# MakeSpaceBadge-2.net
KiCad netlist of a schematic drawn in EAGLE
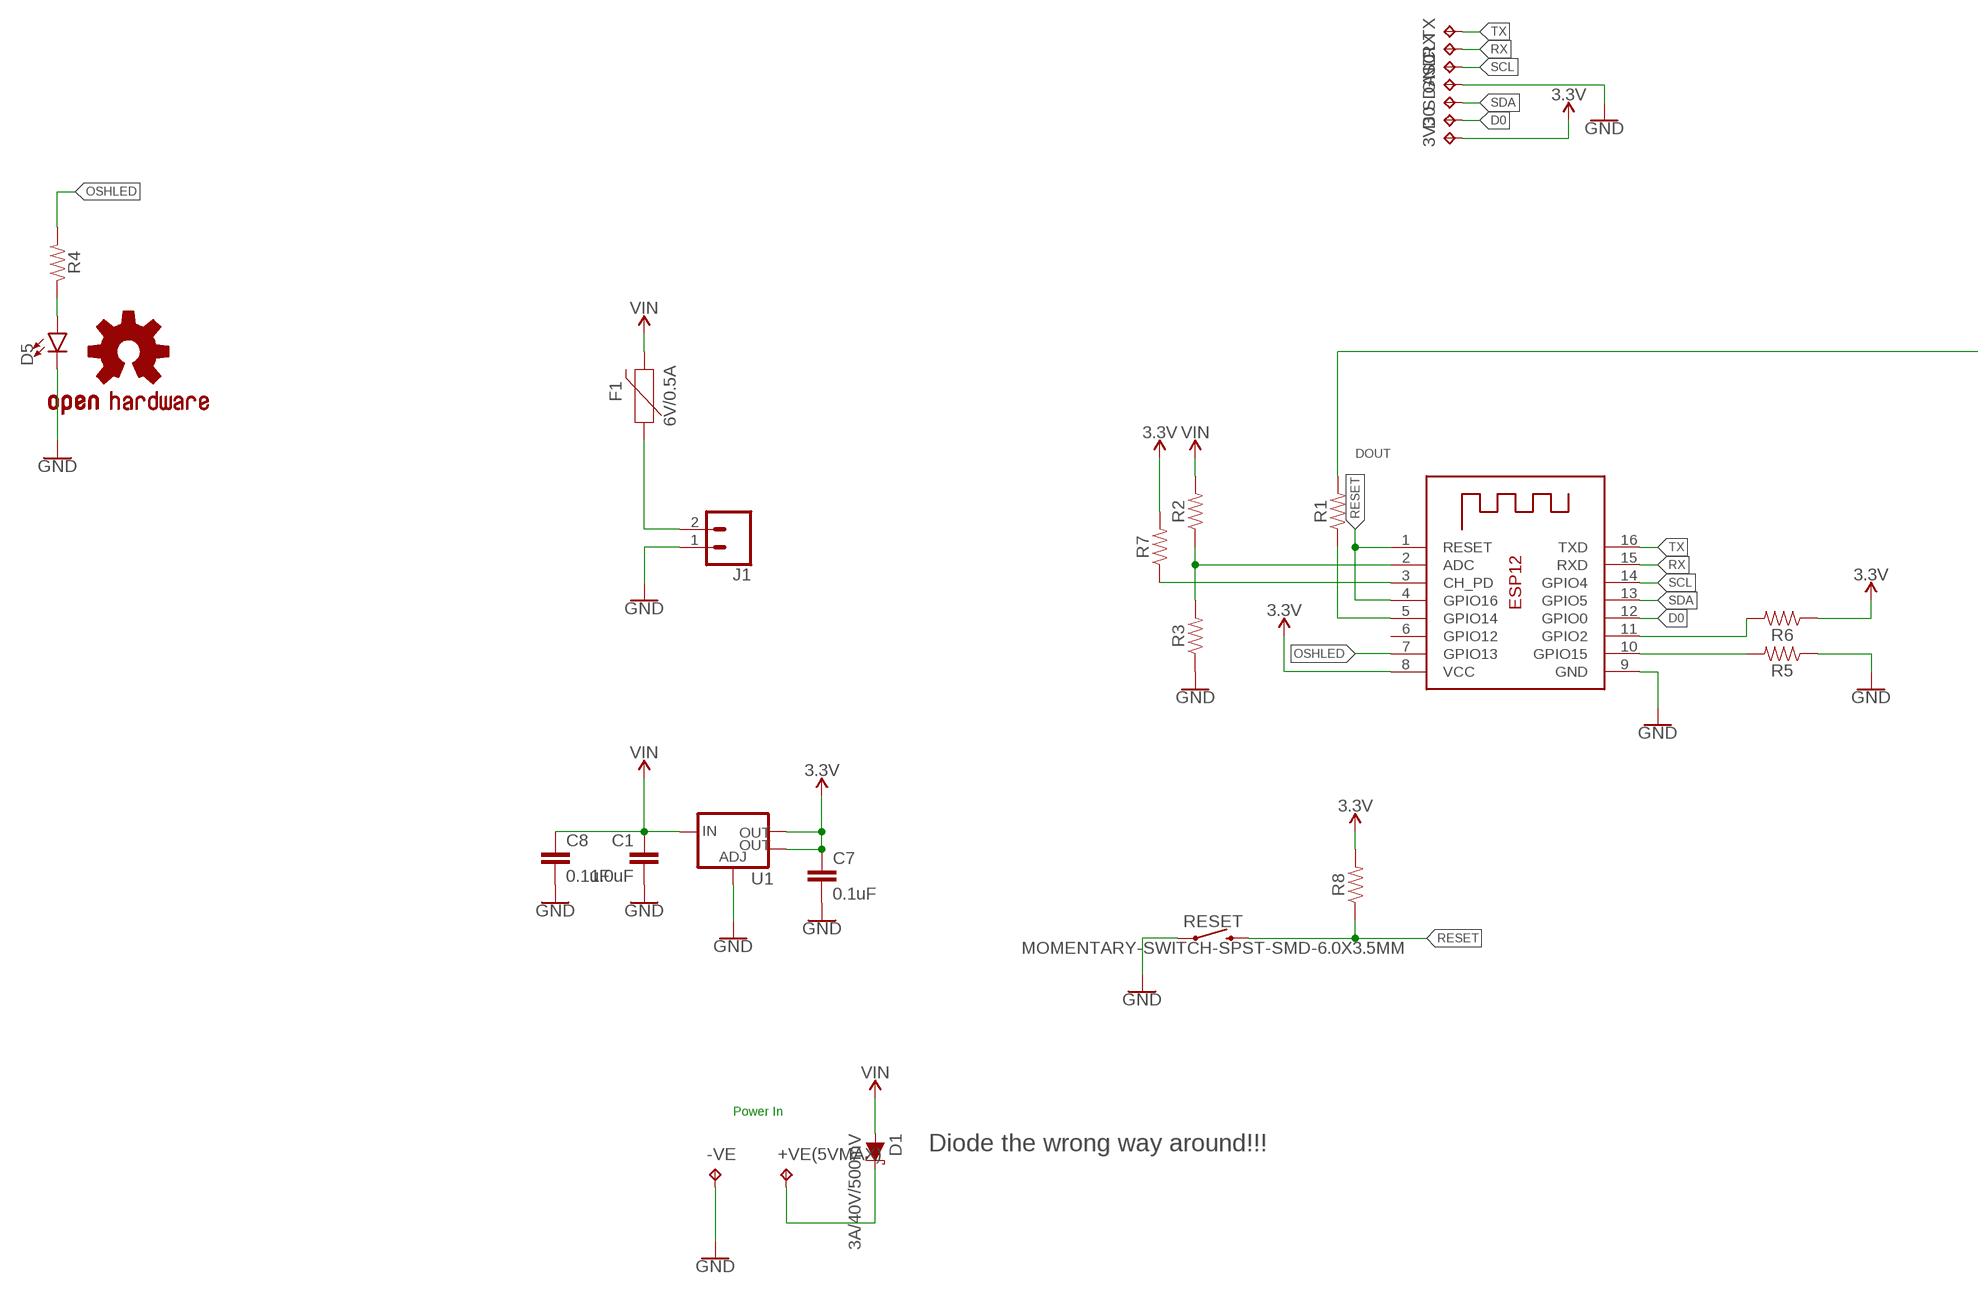
[diagram p0: schematic, sheet 1, part 1 of 2]
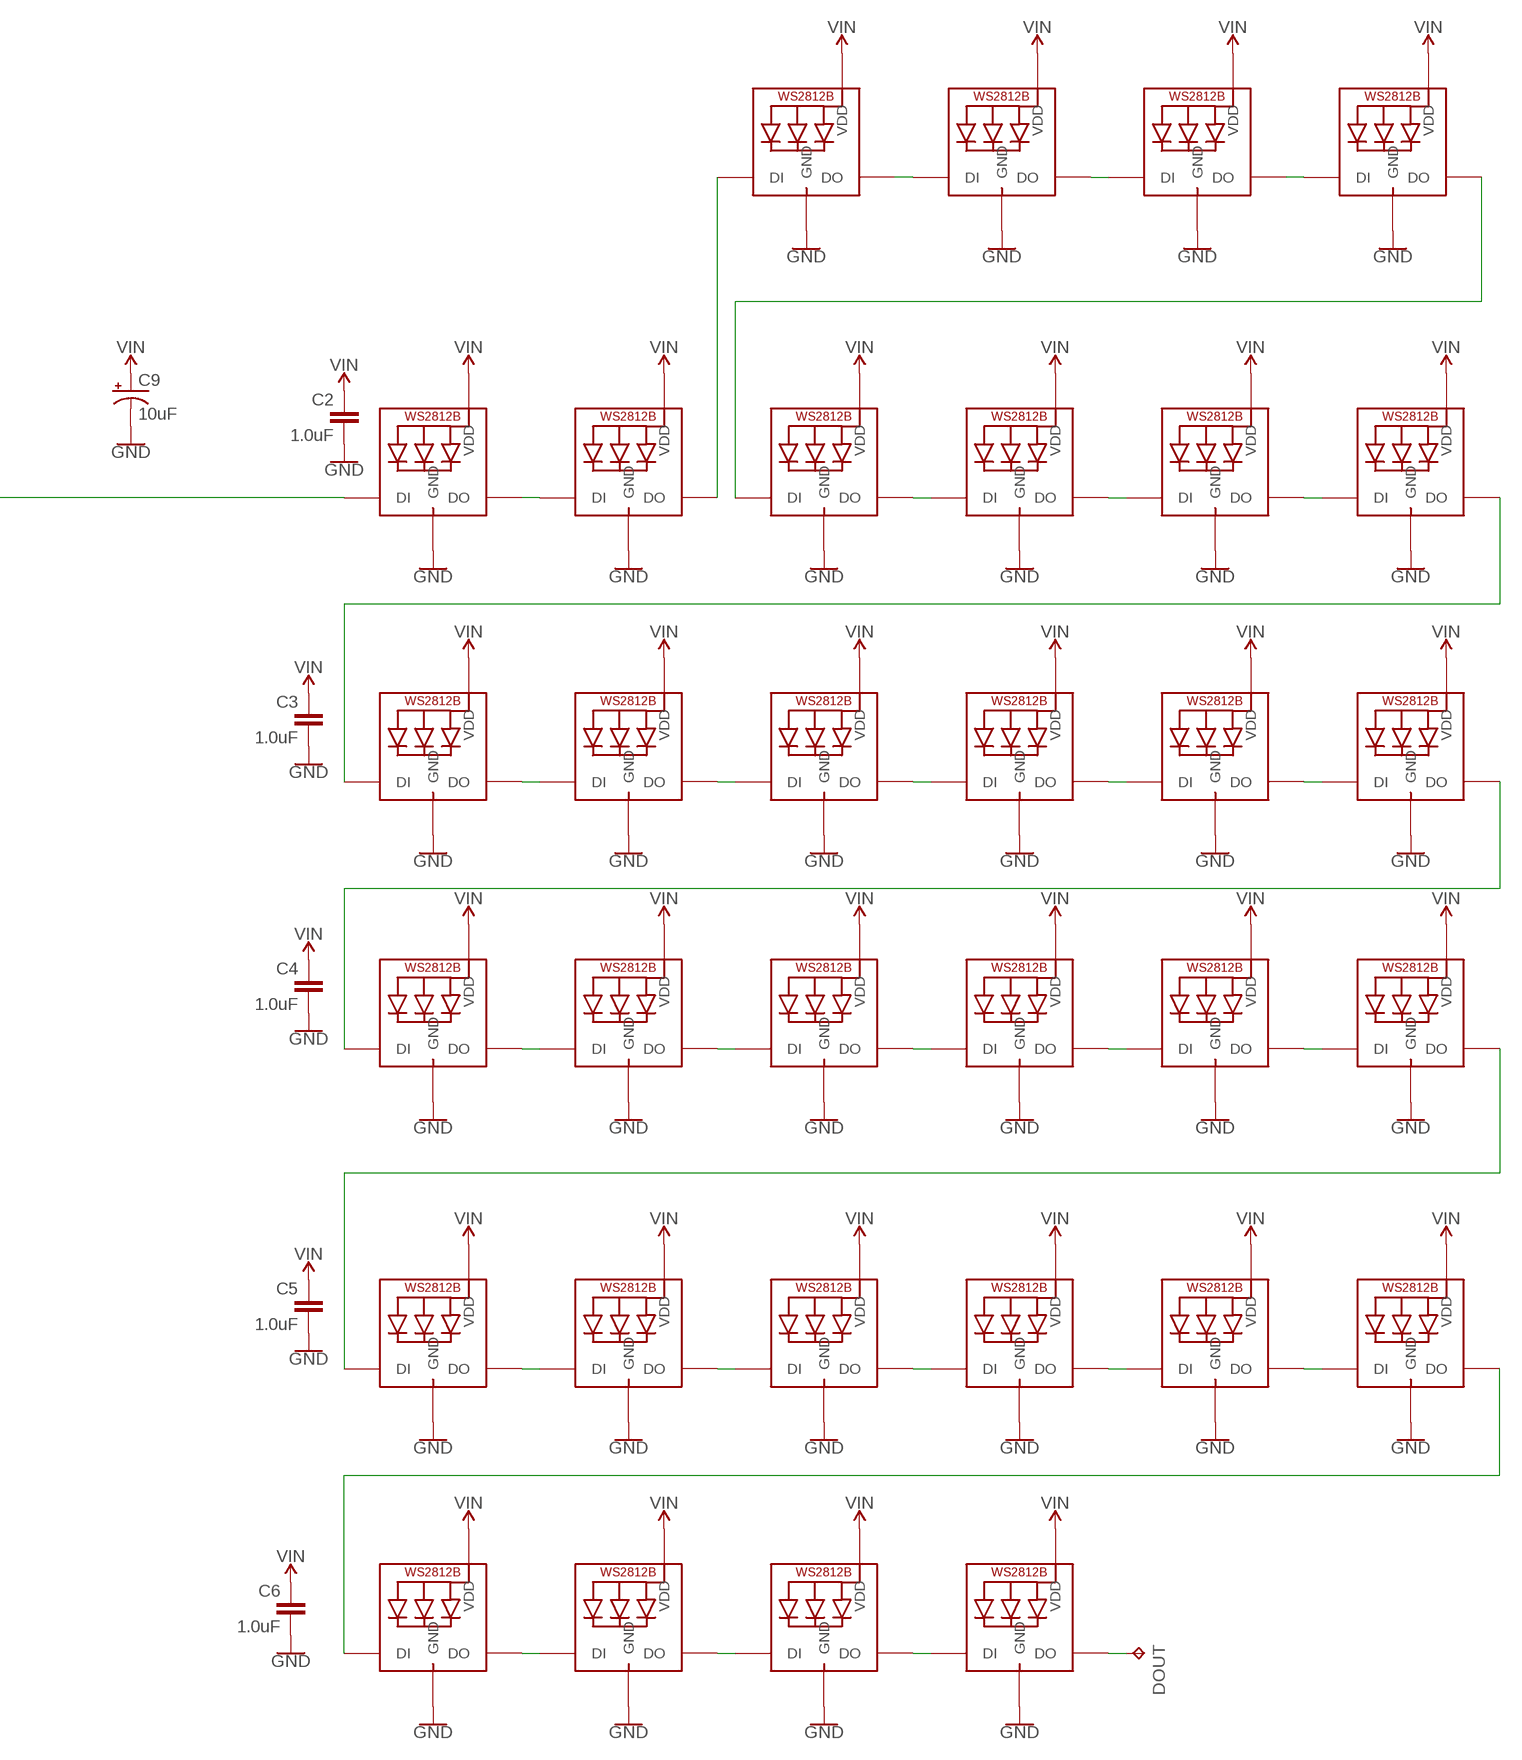
[diagram p1: schematic, sheet 1, part 2 of 2]

(export (version "E")
  (design (tool "Eeschema 10.0.6"))
  (components
    (comp (ref "+VE(5VMAX)")
      (value "TPTP20SQ")
      (footprint "eagle-import:TP20SQ")
      (libsource (lib "eagle-import") (part "TPTP20SQ"))
    )
    (comp (ref "-VE")
      (value "TPTP20SQ")
      (footprint "eagle-import:TP20SQ")
      (libsource (lib "eagle-import") (part "TPTP20SQ"))
    )
    (comp (ref "3V3")
      (value "TPTP20R")
      (footprint "eagle-import:TP20R")
      (libsource (lib "eagle-import") (part "TPTP20R"))
    )
    (comp (ref "C1")
      (value "1.0uF")
      (footprint "eagle-import:0805")
      (libsource (lib "eagle-import") (part "1.0UF-0805-25V-10%"))
    )
    (comp (ref "C2")
      (value "1.0uF")
      (footprint "eagle-import:0805")
      (libsource (lib "eagle-import") (part "1.0UF-0805-25V-10%"))
    )
    (comp (ref "C3")
      (value "1.0uF")
      (footprint "eagle-import:0805")
      (libsource (lib "eagle-import") (part "1.0UF-0805-25V-10%"))
    )
    (comp (ref "C4")
      (value "1.0uF")
      (footprint "eagle-import:0805")
      (libsource (lib "eagle-import") (part "1.0UF-0805-25V-10%"))
    )
    (comp (ref "C5")
      (value "1.0uF")
      (footprint "eagle-import:0805")
      (libsource (lib "eagle-import") (part "1.0UF-0805-25V-10%"))
    )
    (comp (ref "C6")
      (value "1.0uF")
      (footprint "eagle-import:0805")
      (libsource (lib "eagle-import") (part "1.0UF-0805-25V-10%"))
    )
    (comp (ref "C7")
      (value "0.1uF")
      (footprint "eagle-import:0805")
      (libsource (lib "eagle-import") (part "1.0UF-0805-25V-10%"))
    )
    (comp (ref "C8")
      (value "0.1uF")
      (footprint "eagle-import:0805")
      (libsource (lib "eagle-import") (part "1.0UF-0805-25V-10%"))
    )
    (comp (ref "C9")
      (value "10uF")
      (footprint "eagle-import:EIA3216")
      (libsource (lib "eagle-import") (part "10UF-POLAR-EIA3216-16V-10%(TANT)"))
    )
    (comp (ref "D0")
      (value "TPTP20R")
      (footprint "eagle-import:TP20R")
      (libsource (lib "eagle-import") (part "TPTP20R"))
    )
    (comp (ref "D1")
      (value "3A/40V/500mV")
      (footprint "eagle-import:SMA-DIODE")
      (libsource (lib "eagle-import") (part "DIODE-SCHOTTKY-B340A"))
    )
    (comp (ref "D5")
      (value "LED1206-BOTTOM")
      (footprint "eagle-import:LED-1206-BOTTOM")
      (libsource (lib "eagle-import") (part "LED1206-BOTTOM"))
    )
    (comp (ref "DOUT")
      (value "TPTP20R")
      (footprint "eagle-import:TP20R")
      (libsource (lib "eagle-import") (part "TPTP20R"))
    )
    (comp (ref "F1")
      (value "6V/0.5A")
      (footprint "eagle-import:1206")
      (libsource (lib "eagle-import") (part "PPTC_HALF-AMP"))
    )
    (comp (ref "GND")
      (value "TPTP20R")
      (footprint "eagle-import:TP20R")
      (libsource (lib "eagle-import") (part "TPTP20R"))
    )
    (comp (ref "J1")
      (value "CONN_02-JST-2MM-SMT")
      (footprint "eagle-import:JST-2-SMD")
      (libsource (lib "eagle-import") (part "CONN_02-JST-2MM-SMT"))
    )
    (comp (ref "LED1")
      (value "WS2812BBIGPADS")
      (footprint "eagle-import:WS2812B-BIGPADS")
      (libsource (lib "eagle-import") (part "WS2812BBIGPADS"))
    )
    (comp (ref "LED2")
      (value "WS2812B5050")
      (footprint "eagle-import:WS2812B")
      (libsource (lib "eagle-import") (part "WS2812B5050"))
    )
    (comp (ref "LED3")
      (value "WS2812BBIGPADS")
      (footprint "eagle-import:WS2812B-BIGPADS")
      (libsource (lib "eagle-import") (part "WS2812BBIGPADS"))
    )
    (comp (ref "LED4")
      (value "WS2812BBIGPADS")
      (footprint "eagle-import:WS2812B-BIGPADS")
      (libsource (lib "eagle-import") (part "WS2812BBIGPADS"))
    )
    (comp (ref "LED5")
      (value "WS2812BBIGPADS")
      (footprint "eagle-import:WS2812B-BIGPADS")
      (libsource (lib "eagle-import") (part "WS2812BBIGPADS"))
    )
    (comp (ref "LED6")
      (value "WS2812BBIGPADS")
      (footprint "eagle-import:WS2812B-BIGPADS")
      (libsource (lib "eagle-import") (part "WS2812BBIGPADS"))
    )
    (comp (ref "LED7")
      (value "WS2812BBIGPADS")
      (footprint "eagle-import:WS2812B-BIGPADS")
      (libsource (lib "eagle-import") (part "WS2812BBIGPADS"))
    )
    (comp (ref "LED8")
      (value "WS2812BBIGPADS")
      (footprint "eagle-import:WS2812B-BIGPADS")
      (libsource (lib "eagle-import") (part "WS2812BBIGPADS"))
    )
    (comp (ref "LED9")
      (value "WS2812BBIGPADS")
      (footprint "eagle-import:WS2812B-BIGPADS")
      (libsource (lib "eagle-import") (part "WS2812BBIGPADS"))
    )
    (comp (ref "LED10")
      (value "WS2812BBIGPADS")
      (footprint "eagle-import:WS2812B-BIGPADS")
      (libsource (lib "eagle-import") (part "WS2812BBIGPADS"))
    )
    (comp (ref "LED11")
      (value "WS2812BBIGPADS")
      (footprint "eagle-import:WS2812B-BIGPADS")
      (libsource (lib "eagle-import") (part "WS2812BBIGPADS"))
    )
    (comp (ref "LED12")
      (value "WS2812BBIGPADS")
      (footprint "eagle-import:WS2812B-BIGPADS")
      (libsource (lib "eagle-import") (part "WS2812BBIGPADS"))
    )
    (comp (ref "LED13")
      (value "WS2812BBIGPADS")
      (footprint "eagle-import:WS2812B-BIGPADS")
      (libsource (lib "eagle-import") (part "WS2812BBIGPADS"))
    )
    (comp (ref "LED14")
      (value "WS2812BBIGPADS")
      (footprint "eagle-import:WS2812B-BIGPADS")
      (libsource (lib "eagle-import") (part "WS2812BBIGPADS"))
    )
    (comp (ref "LED15")
      (value "WS2812BBIGPADS")
      (footprint "eagle-import:WS2812B-BIGPADS")
      (libsource (lib "eagle-import") (part "WS2812BBIGPADS"))
    )
    (comp (ref "LED16")
      (value "WS2812B5050")
      (footprint "eagle-import:WS2812B")
      (libsource (lib "eagle-import") (part "WS2812B5050"))
    )
    (comp (ref "LED17")
      (value "WS2812BBIGPADS")
      (footprint "eagle-import:WS2812B-BIGPADS")
      (libsource (lib "eagle-import") (part "WS2812BBIGPADS"))
    )
    (comp (ref "LED18")
      (value "WS2812BBIGPADS")
      (footprint "eagle-import:WS2812B-BIGPADS")
      (libsource (lib "eagle-import") (part "WS2812BBIGPADS"))
    )
    (comp (ref "LED19")
      (value "WS2812BBIGPADS")
      (footprint "eagle-import:WS2812B-BIGPADS")
      (libsource (lib "eagle-import") (part "WS2812BBIGPADS"))
    )
    (comp (ref "LED20")
      (value "WS2812BBIGPADS")
      (footprint "eagle-import:WS2812B-BIGPADS")
      (libsource (lib "eagle-import") (part "WS2812BBIGPADS"))
    )
    (comp (ref "LED21")
      (value "WS2812BBIGPADS")
      (footprint "eagle-import:WS2812B-BIGPADS")
      (libsource (lib "eagle-import") (part "WS2812BBIGPADS"))
    )
    (comp (ref "LED22")
      (value "WS2812BBIGPADS")
      (footprint "eagle-import:WS2812B-BIGPADS")
      (libsource (lib "eagle-import") (part "WS2812BBIGPADS"))
    )
    (comp (ref "LED23")
      (value "WS2812BBIGPADS")
      (footprint "eagle-import:WS2812B-BIGPADS")
      (libsource (lib "eagle-import") (part "WS2812BBIGPADS"))
    )
    (comp (ref "LED24")
      (value "WS2812BBIGPADS")
      (footprint "eagle-import:WS2812B-BIGPADS")
      (libsource (lib "eagle-import") (part "WS2812BBIGPADS"))
    )
    (comp (ref "LED25")
      (value "WS2812BBIGPADS")
      (footprint "eagle-import:WS2812B-BIGPADS")
      (libsource (lib "eagle-import") (part "WS2812BBIGPADS"))
    )
    (comp (ref "LED26")
      (value "WS2812BBIGPADS")
      (footprint "eagle-import:WS2812B-BIGPADS")
      (libsource (lib "eagle-import") (part "WS2812BBIGPADS"))
    )
    (comp (ref "LED27")
      (value "WS2812BBIGPADS")
      (footprint "eagle-import:WS2812B-BIGPADS")
      (libsource (lib "eagle-import") (part "WS2812BBIGPADS"))
    )
    (comp (ref "LED28")
      (value "WS2812BBIGPADS")
      (footprint "eagle-import:WS2812B-BIGPADS")
      (libsource (lib "eagle-import") (part "WS2812BBIGPADS"))
    )
    (comp (ref "LED29")
      (value "WS2812BBIGPADS")
      (footprint "eagle-import:WS2812B-BIGPADS")
      (libsource (lib "eagle-import") (part "WS2812BBIGPADS"))
    )
    (comp (ref "LED30")
      (value "WS2812BBIGPADS")
      (footprint "eagle-import:WS2812B-BIGPADS")
      (libsource (lib "eagle-import") (part "WS2812BBIGPADS"))
    )
    (comp (ref "LED31")
      (value "WS2812BBIGPADS")
      (footprint "eagle-import:WS2812B-BIGPADS")
      (libsource (lib "eagle-import") (part "WS2812BBIGPADS"))
    )
    (comp (ref "LED32")
      (value "WS2812BBIGPADS")
      (footprint "eagle-import:WS2812B-BIGPADS")
      (libsource (lib "eagle-import") (part "WS2812BBIGPADS"))
    )
    (comp (ref "LOGO1")
      (value "OSHW-LOGOL")
      (footprint "eagle-import:OSHW-LOGO-L")
      (libsource (lib "eagle-import") (part "OSHW-LOGOL"))
    )
    (comp (ref "R1")
      (value "RESISTOR0805")
      (footprint "eagle-import:0805")
      (libsource (lib "eagle-import") (part "RESISTOR0805"))
    )
    (comp (ref "R2")
      (value "RESISTOR0805")
      (footprint "eagle-import:0805")
      (libsource (lib "eagle-import") (part "RESISTOR0805"))
    )
    (comp (ref "R3")
      (value "RESISTOR0805")
      (footprint "eagle-import:0805")
      (libsource (lib "eagle-import") (part "RESISTOR0805"))
    )
    (comp (ref "R4")
      (value "RESISTOR0805")
      (footprint "eagle-import:0805")
      (libsource (lib "eagle-import") (part "RESISTOR0805"))
    )
    (comp (ref "R5")
      (value "RESISTOR0805")
      (footprint "eagle-import:0805")
      (libsource (lib "eagle-import") (part "RESISTOR0805"))
    )
    (comp (ref "R6")
      (value "RESISTOR0805")
      (footprint "eagle-import:0805")
      (libsource (lib "eagle-import") (part "RESISTOR0805"))
    )
    (comp (ref "R7")
      (value "RESISTOR0805")
      (footprint "eagle-import:0805")
      (libsource (lib "eagle-import") (part "RESISTOR0805"))
    )
    (comp (ref "R8")
      (value "RESISTOR0805")
      (footprint "eagle-import:0805")
      (libsource (lib "eagle-import") (part "RESISTOR0805"))
    )
    (comp (ref "RESET")
      (value "MOMENTARY-SWITCH-SPST-SMD-6.0X3.5MM")
      (footprint "eagle-import:TACTILE_SWITCH_SMD_6.0X3.5MM")
      (libsource (lib "eagle-import") (part "MOMENTARY-SWITCH-SPST-SMD-6.0X3.5MM"))
    )
    (comp (ref "RX")
      (value "TPTP20R")
      (footprint "eagle-import:TP20R")
      (libsource (lib "eagle-import") (part "TPTP20R"))
    )
    (comp (ref "SCL")
      (value "TPTP20R")
      (footprint "eagle-import:TP20R")
      (libsource (lib "eagle-import") (part "TPTP20R"))
    )
    (comp (ref "SDA")
      (value "TPTP20R")
      (footprint "eagle-import:TP20R")
      (libsource (lib "eagle-import") (part "TPTP20R"))
    )
    (comp (ref "TX")
      (value "TPTP20R")
      (footprint "eagle-import:TP20R")
      (libsource (lib "eagle-import") (part "TPTP20R"))
    )
    (comp (ref "U1")
      (value "V_REG_LM1117SOT223")
      (footprint "eagle-import:SOT223")
      (libsource (lib "eagle-import") (part "V_REG_LM1117SOT223"))
    )
    (comp (ref "X1")
      (value "ESP-12")
      (footprint "eagle-import:ESP-12")
      (libsource (lib "eagle-import") (part "ESP-12"))
    )
  )
  (nets
    (net (code "1") (name "/DOUT") (class "Default")
      (node (ref "LED1") (pin "4-DIN") (pinfunction "DI_4-DIN") (pintype "input"))
      (node (ref "R1") (pin "2") (pinfunction "2_2") (pintype "passive"))
    )
    (net (code "2") (name "3.3V") (class "Default")
      (node (ref "3V3") (pin "TP") (pinfunction "TP_TP") (pintype "input"))
      (node (ref "C7") (pin "1") (pinfunction "1_1") (pintype "passive"))
      (node (ref "R6") (pin "1") (pinfunction "1_1") (pintype "passive"))
      (node (ref "R7") (pin "2") (pinfunction "2_2") (pintype "passive"))
      (node (ref "R8") (pin "2") (pinfunction "2_2") (pintype "passive"))
      (node (ref "U1") (pin "2") (pinfunction "OUT_2") (pintype "output"))
      (node (ref "U1") (pin "4") (pinfunction "OUT_4") (pintype "output"))
      (node (ref "X1") (pin "8") (pinfunction "VCC_8") (pintype "power_in"))
    )
    (net (code "3") (name "D0") (class "Default")
      (node (ref "D0") (pin "TP") (pinfunction "TP_TP") (pintype "input"))
      (node (ref "X1") (pin "12") (pinfunction "GPIO0_12") (pintype "bidirectional"))
    )
    (net (code "4") (name "GND") (class "Default")
      (node (ref "-VE") (pin "TP") (pinfunction "TP_TP") (pintype "input"))
      (node (ref "C1") (pin "2") (pinfunction "2_2") (pintype "passive"))
      (node (ref "C2") (pin "2") (pinfunction "2_2") (pintype "passive"))
      (node (ref "C3") (pin "2") (pinfunction "2_2") (pintype "passive"))
      (node (ref "C4") (pin "2") (pinfunction "2_2") (pintype "passive"))
      (node (ref "C5") (pin "2") (pinfunction "2_2") (pintype "passive"))
      (node (ref "C6") (pin "2") (pinfunction "2_2") (pintype "passive"))
      (node (ref "C7") (pin "2") (pinfunction "2_2") (pintype "passive"))
      (node (ref "C8") (pin "2") (pinfunction "2_2") (pintype "passive"))
      (node (ref "C9") (pin "-") (pinfunction "-_-") (pintype "passive"))
      (node (ref "D5") (pin "C") (pinfunction "C_C") (pintype "passive"))
      (node (ref "GND") (pin "TP") (pinfunction "TP_TP") (pintype "input"))
      (node (ref "J1") (pin "1") (pinfunction "2_1") (pintype "passive"))
      (node (ref "LED1") (pin "3-GND") (pinfunction "GND_3-GND") (pintype "power_in"))
      (node (ref "LED10") (pin "3-GND") (pinfunction "GND_3-GND") (pintype "power_in"))
      (node (ref "LED11") (pin "3-GND") (pinfunction "GND_3-GND") (pintype "power_in"))
      (node (ref "LED12") (pin "3-GND") (pinfunction "GND_3-GND") (pintype "power_in"))
      (node (ref "LED13") (pin "3-GND") (pinfunction "GND_3-GND") (pintype "power_in"))
      (node (ref "LED14") (pin "3-GND") (pinfunction "GND_3-GND") (pintype "power_in"))
      (node (ref "LED15") (pin "3-GND") (pinfunction "GND_3-GND") (pintype "power_in"))
      (node (ref "LED16") (pin "3-GND") (pinfunction "GND_3-GND") (pintype "power_in"))
      (node (ref "LED17") (pin "3-GND") (pinfunction "GND_3-GND") (pintype "power_in"))
      (node (ref "LED18") (pin "3-GND") (pinfunction "GND_3-GND") (pintype "power_in"))
      (node (ref "LED19") (pin "3-GND") (pinfunction "GND_3-GND") (pintype "power_in"))
      (node (ref "LED2") (pin "3-GND") (pinfunction "GND_3-GND") (pintype "power_in"))
      (node (ref "LED20") (pin "3-GND") (pinfunction "GND_3-GND") (pintype "power_in"))
      (node (ref "LED21") (pin "3-GND") (pinfunction "GND_3-GND") (pintype "power_in"))
      (node (ref "LED22") (pin "3-GND") (pinfunction "GND_3-GND") (pintype "power_in"))
      (node (ref "LED23") (pin "3-GND") (pinfunction "GND_3-GND") (pintype "power_in"))
      (node (ref "LED24") (pin "3-GND") (pinfunction "GND_3-GND") (pintype "power_in"))
      (node (ref "LED25") (pin "3-GND") (pinfunction "GND_3-GND") (pintype "power_in"))
      (node (ref "LED26") (pin "3-GND") (pinfunction "GND_3-GND") (pintype "power_in"))
      (node (ref "LED27") (pin "3-GND") (pinfunction "GND_3-GND") (pintype "power_in"))
      (node (ref "LED28") (pin "3-GND") (pinfunction "GND_3-GND") (pintype "power_in"))
      (node (ref "LED29") (pin "3-GND") (pinfunction "GND_3-GND") (pintype "power_in"))
      (node (ref "LED3") (pin "3-GND") (pinfunction "GND_3-GND") (pintype "power_in"))
      (node (ref "LED30") (pin "3-GND") (pinfunction "GND_3-GND") (pintype "power_in"))
      (node (ref "LED31") (pin "3-GND") (pinfunction "GND_3-GND") (pintype "power_in"))
      (node (ref "LED32") (pin "3-GND") (pinfunction "GND_3-GND") (pintype "power_in"))
      (node (ref "LED4") (pin "3-GND") (pinfunction "GND_3-GND") (pintype "power_in"))
      (node (ref "LED5") (pin "3-GND") (pinfunction "GND_3-GND") (pintype "power_in"))
      (node (ref "LED6") (pin "3-GND") (pinfunction "GND_3-GND") (pintype "power_in"))
      (node (ref "LED7") (pin "3-GND") (pinfunction "GND_3-GND") (pintype "power_in"))
      (node (ref "LED8") (pin "3-GND") (pinfunction "GND_3-GND") (pintype "power_in"))
      (node (ref "LED9") (pin "3-GND") (pinfunction "GND_3-GND") (pintype "power_in"))
      (node (ref "R3") (pin "1") (pinfunction "1_1") (pintype "passive"))
      (node (ref "R5") (pin "1") (pinfunction "1_1") (pintype "passive"))
      (node (ref "RESET") (pin "1") (pinfunction "1_1") (pintype "passive"))
      (node (ref "U1") (pin "1") (pinfunction "ADJ_1") (pintype "input"))
      (node (ref "X1") (pin "9") (pinfunction "GND_9") (pintype "power_in"))
    )
    (net (code "5") (name "Net-(+VE(5VMAX)-PadTP)") (class "Default")
      (node (ref "+VE(5VMAX)") (pin "TP") (pinfunction "TP_TP") (pintype "input"))
      (node (ref "D1") (pin "C") (pinfunction "C_C") (pintype "passive"))
    )
    (net (code "6") (name "Net-(D5-PadA)") (class "Default")
      (node (ref "D5") (pin "A") (pinfunction "A_A") (pintype "passive"))
      (node (ref "R4") (pin "1") (pinfunction "1_1") (pintype "passive"))
    )
    (net (code "7") (name "Net-(J1-1)") (class "Default")
      (node (ref "F1") (pin "1") (pinfunction "1_1") (pintype "bidirectional"))
      (node (ref "J1") (pin "2") (pinfunction "1_2") (pintype "passive"))
    )
    (net (code "8") (name "Net-(LED1-DO)") (class "Default")
      (node (ref "LED1") (pin "2-DOUT") (pinfunction "DO_2-DOUT") (pintype "output"))
      (node (ref "LED2") (pin "4-DIN") (pinfunction "DI_4-DIN") (pintype "input"))
    )
    (net (code "9") (name "Net-(LED2-DO)") (class "Default")
      (node (ref "LED2") (pin "2-DOUT") (pinfunction "DO_2-DOUT") (pintype "output"))
      (node (ref "LED24") (pin "4-DIN") (pinfunction "DI_4-DIN") (pintype "input"))
    )
    (net (code "10") (name "Net-(LED3-DI)") (class "Default")
      (node (ref "LED3") (pin "4-DIN") (pinfunction "DI_4-DIN") (pintype "input"))
      (node (ref "LED32") (pin "2-DOUT") (pinfunction "DO_2-DOUT") (pintype "output"))
    )
    (net (code "11") (name "Net-(LED3-DO)") (class "Default")
      (node (ref "LED3") (pin "2-DOUT") (pinfunction "DO_2-DOUT") (pintype "output"))
      (node (ref "LED4") (pin "4-DIN") (pinfunction "DI_4-DIN") (pintype "input"))
    )
    (net (code "12") (name "Net-(LED4-DO)") (class "Default")
      (node (ref "LED4") (pin "2-DOUT") (pinfunction "DO_2-DOUT") (pintype "output"))
      (node (ref "LED5") (pin "4-DIN") (pinfunction "DI_4-DIN") (pintype "input"))
    )
    (net (code "13") (name "Net-(LED5-DO)") (class "Default")
      (node (ref "LED5") (pin "2-DOUT") (pinfunction "DO_2-DOUT") (pintype "output"))
      (node (ref "LED6") (pin "4-DIN") (pinfunction "DI_4-DIN") (pintype "input"))
    )
    (net (code "14") (name "Net-(LED6-DO)") (class "Default")
      (node (ref "LED6") (pin "2-DOUT") (pinfunction "DO_2-DOUT") (pintype "output"))
      (node (ref "LED7") (pin "4-DIN") (pinfunction "DI_4-DIN") (pintype "input"))
    )
    (net (code "15") (name "Net-(LED7-DO)") (class "Default")
      (node (ref "LED7") (pin "2-DOUT") (pinfunction "DO_2-DOUT") (pintype "output"))
      (node (ref "LED8") (pin "4-DIN") (pinfunction "DI_4-DIN") (pintype "input"))
    )
    (net (code "16") (name "Net-(LED8-DO)") (class "Default")
      (node (ref "LED8") (pin "2-DOUT") (pinfunction "DO_2-DOUT") (pintype "output"))
      (node (ref "LED9") (pin "4-DIN") (pinfunction "DI_4-DIN") (pintype "input"))
    )
    (net (code "17") (name "Net-(LED10-DI)") (class "Default")
      (node (ref "LED10") (pin "4-DIN") (pinfunction "DI_4-DIN") (pintype "input"))
      (node (ref "LED9") (pin "2-DOUT") (pinfunction "DO_2-DOUT") (pintype "output"))
    )
    (net (code "18") (name "Net-(LED10-DO)") (class "Default")
      (node (ref "LED10") (pin "2-DOUT") (pinfunction "DO_2-DOUT") (pintype "output"))
      (node (ref "LED11") (pin "4-DIN") (pinfunction "DI_4-DIN") (pintype "input"))
    )
    (net (code "19") (name "Net-(LED11-DO)") (class "Default")
      (node (ref "LED11") (pin "2-DOUT") (pinfunction "DO_2-DOUT") (pintype "output"))
      (node (ref "LED12") (pin "4-DIN") (pinfunction "DI_4-DIN") (pintype "input"))
    )
    (net (code "20") (name "Net-(LED12-DO)") (class "Default")
      (node (ref "LED12") (pin "2-DOUT") (pinfunction "DO_2-DOUT") (pintype "output"))
      (node (ref "LED13") (pin "4-DIN") (pinfunction "DI_4-DIN") (pintype "input"))
    )
    (net (code "21") (name "Net-(LED13-DO)") (class "Default")
      (node (ref "LED13") (pin "2-DOUT") (pinfunction "DO_2-DOUT") (pintype "output"))
      (node (ref "LED14") (pin "4-DIN") (pinfunction "DI_4-DIN") (pintype "input"))
    )
    (net (code "22") (name "Net-(LED14-DO)") (class "Default")
      (node (ref "LED14") (pin "2-DOUT") (pinfunction "DO_2-DOUT") (pintype "output"))
      (node (ref "LED15") (pin "4-DIN") (pinfunction "DI_4-DIN") (pintype "input"))
    )
    (net (code "23") (name "Net-(LED15-DO)") (class "Default")
      (node (ref "LED15") (pin "2-DOUT") (pinfunction "DO_2-DOUT") (pintype "output"))
      (node (ref "LED16") (pin "4-DIN") (pinfunction "DI_4-DIN") (pintype "input"))
    )
    (net (code "24") (name "Net-(LED16-DO)") (class "Default")
      (node (ref "LED16") (pin "2-DOUT") (pinfunction "DO_2-DOUT") (pintype "output"))
      (node (ref "LED17") (pin "4-DIN") (pinfunction "DI_4-DIN") (pintype "input"))
    )
    (net (code "25") (name "Net-(LED17-DO)") (class "Default")
      (node (ref "LED17") (pin "2-DOUT") (pinfunction "DO_2-DOUT") (pintype "output"))
      (node (ref "LED18") (pin "4-DIN") (pinfunction "DI_4-DIN") (pintype "input"))
    )
    (net (code "26") (name "Net-(LED18-DO)") (class "Default")
      (node (ref "LED18") (pin "2-DOUT") (pinfunction "DO_2-DOUT") (pintype "output"))
      (node (ref "LED19") (pin "4-DIN") (pinfunction "DI_4-DIN") (pintype "input"))
    )
    (net (code "27") (name "Net-(LED19-DO)") (class "Default")
      (node (ref "LED19") (pin "2-DOUT") (pinfunction "DO_2-DOUT") (pintype "output"))
      (node (ref "LED20") (pin "4-DIN") (pinfunction "DI_4-DIN") (pintype "input"))
    )
    (net (code "28") (name "Net-(LED20-DO)") (class "Default")
      (node (ref "LED20") (pin "2-DOUT") (pinfunction "DO_2-DOUT") (pintype "output"))
      (node (ref "LED21") (pin "4-DIN") (pinfunction "DI_4-DIN") (pintype "input"))
    )
    (net (code "29") (name "Net-(LED21-DO)") (class "Default")
      (node (ref "LED21") (pin "2-DOUT") (pinfunction "DO_2-DOUT") (pintype "output"))
      (node (ref "LED25") (pin "4-DIN") (pinfunction "DI_4-DIN") (pintype "input"))
    )
    (net (code "30") (name "Net-(LED22-DI)") (class "Default")
      (node (ref "LED22") (pin "4-DIN") (pinfunction "DI_4-DIN") (pintype "input"))
      (node (ref "LED23") (pin "2-DOUT") (pinfunction "DO_2-DOUT") (pintype "output"))
    )
    (net (code "31") (name "Net-(LED22-DO)") (class "Default")
      (node (ref "LED22") (pin "2-DOUT") (pinfunction "DO_2-DOUT") (pintype "output"))
      (node (ref "LED32") (pin "4-DIN") (pinfunction "DI_4-DIN") (pintype "input"))
    )
    (net (code "32") (name "Net-(LED23-DI)") (class "Default")
      (node (ref "LED23") (pin "4-DIN") (pinfunction "DI_4-DIN") (pintype "input"))
      (node (ref "LED24") (pin "2-DOUT") (pinfunction "DO_2-DOUT") (pintype "output"))
    )
    (net (code "33") (name "Net-(LED25-DO)") (class "Default")
      (node (ref "LED25") (pin "2-DOUT") (pinfunction "DO_2-DOUT") (pintype "output"))
      (node (ref "LED26") (pin "4-DIN") (pinfunction "DI_4-DIN") (pintype "input"))
    )
    (net (code "34") (name "Net-(LED26-DO)") (class "Default")
      (node (ref "LED26") (pin "2-DOUT") (pinfunction "DO_2-DOUT") (pintype "output"))
      (node (ref "LED27") (pin "4-DIN") (pinfunction "DI_4-DIN") (pintype "input"))
    )
    (net (code "35") (name "Net-(LED27-DO)") (class "Default")
      (node (ref "LED27") (pin "2-DOUT") (pinfunction "DO_2-DOUT") (pintype "output"))
      (node (ref "LED28") (pin "4-DIN") (pinfunction "DI_4-DIN") (pintype "input"))
    )
    (net (code "36") (name "Net-(LED28-DO)") (class "Default")
      (node (ref "LED28") (pin "2-DOUT") (pinfunction "DO_2-DOUT") (pintype "output"))
      (node (ref "LED29") (pin "4-DIN") (pinfunction "DI_4-DIN") (pintype "input"))
    )
    (net (code "37") (name "Net-(LED29-DO)") (class "Default")
      (node (ref "LED29") (pin "2-DOUT") (pinfunction "DO_2-DOUT") (pintype "output"))
      (node (ref "LED30") (pin "4-DIN") (pinfunction "DI_4-DIN") (pintype "input"))
    )
    (net (code "38") (name "Net-(LED30-DO)") (class "Default")
      (node (ref "LED30") (pin "2-DOUT") (pinfunction "DO_2-DOUT") (pintype "output"))
      (node (ref "LED31") (pin "4-DIN") (pinfunction "DI_4-DIN") (pintype "input"))
    )
    (net (code "39") (name "Net-(LED31-DO)") (class "Default")
      (node (ref "DOUT") (pin "TP") (pinfunction "TP_TP") (pintype "input"))
      (node (ref "LED31") (pin "2-DOUT") (pinfunction "DO_2-DOUT") (pintype "output"))
    )
    (net (code "40") (name "Net-(X1-ADC)") (class "Default")
      (node (ref "R2") (pin "1") (pinfunction "1_1") (pintype "passive"))
      (node (ref "R3") (pin "2") (pinfunction "2_2") (pintype "passive"))
      (node (ref "X1") (pin "2") (pinfunction "ADC_2") (pintype "passive"))
    )
    (net (code "41") (name "Net-(X1-CH_PD)") (class "Default")
      (node (ref "R7") (pin "1") (pinfunction "1_1") (pintype "passive"))
      (node (ref "X1") (pin "3") (pinfunction "CH_PD_3") (pintype "input"))
    )
    (net (code "42") (name "Net-(X1-GPIO2)") (class "Default")
      (node (ref "R6") (pin "2") (pinfunction "2_2") (pintype "passive"))
      (node (ref "X1") (pin "11") (pinfunction "GPIO2_11") (pintype "bidirectional"))
    )
    (net (code "43") (name "Net-(X1-GPIO14)") (class "Default")
      (node (ref "R1") (pin "1") (pinfunction "1_1") (pintype "passive"))
      (node (ref "X1") (pin "5") (pinfunction "GPIO14_5") (pintype "bidirectional"))
    )
    (net (code "44") (name "Net-(X1-GPIO15)") (class "Default")
      (node (ref "R5") (pin "2") (pinfunction "2_2") (pintype "passive"))
      (node (ref "X1") (pin "10") (pinfunction "GPIO15_10") (pintype "bidirectional"))
    )
    (net (code "45") (name "OSHLED") (class "Default")
      (node (ref "R4") (pin "2") (pinfunction "2_2") (pintype "passive"))
      (node (ref "X1") (pin "7") (pinfunction "GPIO13_7") (pintype "bidirectional"))
    )
    (net (code "46") (name "RESET") (class "Default")
      (node (ref "R8") (pin "1") (pinfunction "1_1") (pintype "passive"))
      (node (ref "RESET") (pin "2") (pinfunction "2_2") (pintype "passive"))
      (node (ref "X1") (pin "1") (pinfunction "RESET_1") (pintype "input"))
      (node (ref "X1") (pin "4") (pinfunction "GPIO16_4") (pintype "bidirectional"))
    )
    (net (code "47") (name "RX") (class "Default")
      (node (ref "RX") (pin "TP") (pinfunction "TP_TP") (pintype "input"))
      (node (ref "X1") (pin "15") (pinfunction "RXD_15") (pintype "input"))
    )
    (net (code "48") (name "SCL") (class "Default")
      (node (ref "SCL") (pin "TP") (pinfunction "TP_TP") (pintype "input"))
      (node (ref "X1") (pin "14") (pinfunction "GPIO4_14") (pintype "bidirectional"))
    )
    (net (code "49") (name "SDA") (class "Default")
      (node (ref "SDA") (pin "TP") (pinfunction "TP_TP") (pintype "input"))
      (node (ref "X1") (pin "13") (pinfunction "GPIO5_13") (pintype "bidirectional"))
    )
    (net (code "50") (name "TX") (class "Default")
      (node (ref "TX") (pin "TP") (pinfunction "TP_TP") (pintype "input"))
      (node (ref "X1") (pin "16") (pinfunction "TXD_16") (pintype "output"))
    )
    (net (code "51") (name "VIN") (class "Default")
      (node (ref "C1") (pin "1") (pinfunction "1_1") (pintype "passive"))
      (node (ref "C2") (pin "1") (pinfunction "1_1") (pintype "passive"))
      (node (ref "C3") (pin "1") (pinfunction "1_1") (pintype "passive"))
      (node (ref "C4") (pin "1") (pinfunction "1_1") (pintype "passive"))
      (node (ref "C5") (pin "1") (pinfunction "1_1") (pintype "passive"))
      (node (ref "C6") (pin "1") (pinfunction "1_1") (pintype "passive"))
      (node (ref "C8") (pin "1") (pinfunction "1_1") (pintype "passive"))
      (node (ref "C9") (pin "+") (pinfunction "+_+") (pintype "passive"))
      (node (ref "D1") (pin "A") (pinfunction "A_A") (pintype "passive"))
      (node (ref "F1") (pin "2") (pinfunction "2_2") (pintype "bidirectional"))
      (node (ref "LED1") (pin "1-VDD") (pinfunction "VDD_1-VDD") (pintype "power_in"))
      (node (ref "LED10") (pin "1-VDD") (pinfunction "VDD_1-VDD") (pintype "power_in"))
      (node (ref "LED11") (pin "1-VDD") (pinfunction "VDD_1-VDD") (pintype "power_in"))
      (node (ref "LED12") (pin "1-VDD") (pinfunction "VDD_1-VDD") (pintype "power_in"))
      (node (ref "LED13") (pin "1-VDD") (pinfunction "VDD_1-VDD") (pintype "power_in"))
      (node (ref "LED14") (pin "1-VDD") (pinfunction "VDD_1-VDD") (pintype "power_in"))
      (node (ref "LED15") (pin "1-VDD") (pinfunction "VDD_1-VDD") (pintype "power_in"))
      (node (ref "LED16") (pin "1-VDD") (pinfunction "VDD_1-VDD") (pintype "power_in"))
      (node (ref "LED17") (pin "1-VDD") (pinfunction "VDD_1-VDD") (pintype "power_in"))
      (node (ref "LED18") (pin "1-VDD") (pinfunction "VDD_1-VDD") (pintype "power_in"))
      (node (ref "LED19") (pin "1-VDD") (pinfunction "VDD_1-VDD") (pintype "power_in"))
      (node (ref "LED2") (pin "1-VDD") (pinfunction "VDD_1-VDD") (pintype "power_in"))
      (node (ref "LED20") (pin "1-VDD") (pinfunction "VDD_1-VDD") (pintype "power_in"))
      (node (ref "LED21") (pin "1-VDD") (pinfunction "VDD_1-VDD") (pintype "power_in"))
      (node (ref "LED22") (pin "1-VDD") (pinfunction "VDD_1-VDD") (pintype "power_in"))
      (node (ref "LED23") (pin "1-VDD") (pinfunction "VDD_1-VDD") (pintype "power_in"))
      (node (ref "LED24") (pin "1-VDD") (pinfunction "VDD_1-VDD") (pintype "power_in"))
      (node (ref "LED25") (pin "1-VDD") (pinfunction "VDD_1-VDD") (pintype "power_in"))
      (node (ref "LED26") (pin "1-VDD") (pinfunction "VDD_1-VDD") (pintype "power_in"))
      (node (ref "LED27") (pin "1-VDD") (pinfunction "VDD_1-VDD") (pintype "power_in"))
      (node (ref "LED28") (pin "1-VDD") (pinfunction "VDD_1-VDD") (pintype "power_in"))
      (node (ref "LED29") (pin "1-VDD") (pinfunction "VDD_1-VDD") (pintype "power_in"))
      (node (ref "LED3") (pin "1-VDD") (pinfunction "VDD_1-VDD") (pintype "power_in"))
      (node (ref "LED30") (pin "1-VDD") (pinfunction "VDD_1-VDD") (pintype "power_in"))
      (node (ref "LED31") (pin "1-VDD") (pinfunction "VDD_1-VDD") (pintype "power_in"))
      (node (ref "LED32") (pin "1-VDD") (pinfunction "VDD_1-VDD") (pintype "power_in"))
      (node (ref "LED4") (pin "1-VDD") (pinfunction "VDD_1-VDD") (pintype "power_in"))
      (node (ref "LED5") (pin "1-VDD") (pinfunction "VDD_1-VDD") (pintype "power_in"))
      (node (ref "LED6") (pin "1-VDD") (pinfunction "VDD_1-VDD") (pintype "power_in"))
      (node (ref "LED7") (pin "1-VDD") (pinfunction "VDD_1-VDD") (pintype "power_in"))
      (node (ref "LED8") (pin "1-VDD") (pinfunction "VDD_1-VDD") (pintype "power_in"))
      (node (ref "LED9") (pin "1-VDD") (pinfunction "VDD_1-VDD") (pintype "power_in"))
      (node (ref "R2") (pin "2") (pinfunction "2_2") (pintype "passive"))
      (node (ref "U1") (pin "3") (pinfunction "IN_3") (pintype "input"))
    )
    (net (code "52") (name "unconnected-(X1-GPIO12-Pad6)") (class "Default")
      (node (ref "X1") (pin "6") (pinfunction "GPIO12_6") (pintype "bidirectional"))
    )
  )
)
